# power_injector_0_7.net
KiCad netlist of a schematic drawn in EAGLE
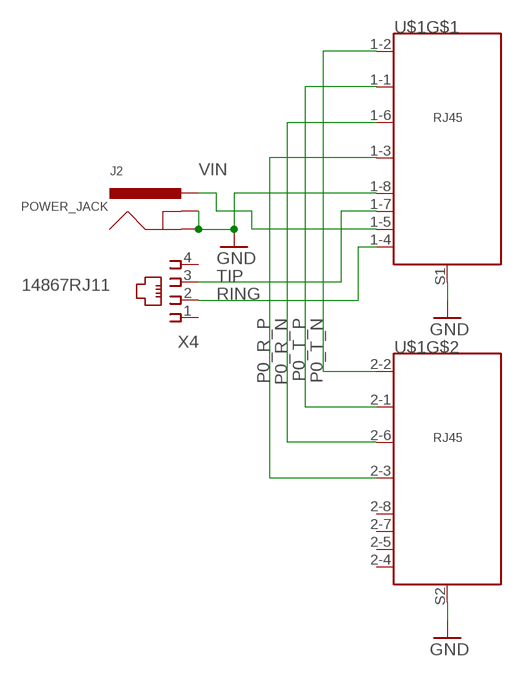
[diagram p0: schematic, sheet 1]

(export (version "E")
  (design (tool "Eeschema 10.0.6"))
  (components
    (comp (ref "J2")
      (value "POWER_JACK")
      (footprint "eagle-import:POWER_JACK_SLOT1")
      (libsource (lib "eagle-import") (part "POWER_JACK"))
    )
    (comp (ref "U$1")
      (value "ETHERNET_2PORT")
      (footprint "eagle-import:ETHERNET-1X2")
      (libsource (lib "eagle-import") (part "ETHERNET_2PORT"))
    )
    (comp (ref "X4")
      (value "14867RJ11")
      (footprint "eagle-import:14867")
      (libsource (lib "eagle-import") (part "14867RJ11"))
    )
  )
  (nets
    (net (code "1") (name "/P0_R_N") (class "Default")
      (node (ref "U$1") (pin "1-6") (pinfunction "6_1-6") (pintype "passive"))
      (node (ref "U$1") (pin "2-6") (pinfunction "6_2-6") (pintype "passive"))
    )
    (net (code "2") (name "/P0_R_P") (class "Default")
      (node (ref "U$1") (pin "1-3") (pinfunction "3_1-3") (pintype "passive"))
      (node (ref "U$1") (pin "2-3") (pinfunction "3_2-3") (pintype "passive"))
    )
    (net (code "3") (name "/P0_T_N") (class "Default")
      (node (ref "U$1") (pin "1-2") (pinfunction "2_1-2") (pintype "passive"))
      (node (ref "U$1") (pin "2-2") (pinfunction "2_2-2") (pintype "passive"))
    )
    (net (code "4") (name "/P0_T_P") (class "Default")
      (node (ref "U$1") (pin "1-1") (pinfunction "1_1-1") (pintype "passive"))
      (node (ref "U$1") (pin "2-1") (pinfunction "1_2-1") (pintype "passive"))
    )
    (net (code "5") (name "/RING") (class "Default")
      (node (ref "U$1") (pin "1-4") (pinfunction "4_1-4") (pintype "passive"))
      (node (ref "X4") (pin "2") (pinfunction "2_2") (pintype "passive"))
    )
    (net (code "6") (name "/TIP") (class "Default")
      (node (ref "U$1") (pin "1-7") (pinfunction "7_1-7") (pintype "passive"))
      (node (ref "X4") (pin "3") (pinfunction "3_3") (pintype "passive"))
    )
    (net (code "7") (name "/VIN") (class "Default")
      (node (ref "J2") (pin "PWR") (pinfunction "PWR_PWR") (pintype "bidirectional"))
      (node (ref "U$1") (pin "1-5") (pinfunction "5_1-5") (pintype "passive"))
    )
    (net (code "8") (name "GND") (class "Default")
      (node (ref "J2") (pin "GND@1") (pinfunction "GNDBREAK_GND@1") (pintype "bidirectional"))
      (node (ref "J2") (pin "GND@2") (pinfunction "GND_GND@2") (pintype "bidirectional"))
      (node (ref "U$1") (pin "1-8") (pinfunction "8_1-8") (pintype "passive"))
      (node (ref "U$1") (pin "S1") (pinfunction "SHIELD_S1") (pintype "power_in"))
      (node (ref "U$1") (pin "S2") (pinfunction "SHIELD_S2") (pintype "power_in"))
    )
    (net (code "9") (name "unconnected-(U$1B-4-Pad2-4)") (class "Default")
      (node (ref "U$1") (pin "2-4") (pinfunction "4_2-4") (pintype "passive"))
    )
    (net (code "10") (name "unconnected-(U$1B-5-Pad2-5)") (class "Default")
      (node (ref "U$1") (pin "2-5") (pinfunction "5_2-5") (pintype "passive"))
    )
    (net (code "11") (name "unconnected-(U$1B-7-Pad2-7)") (class "Default")
      (node (ref "U$1") (pin "2-7") (pinfunction "7_2-7") (pintype "passive"))
    )
    (net (code "12") (name "unconnected-(U$1B-8-Pad2-8)") (class "Default")
      (node (ref "U$1") (pin "2-8") (pinfunction "8_2-8") (pintype "passive"))
    )
    (net (code "13") (name "unconnected-(X4-Pad1)") (class "Default")
      (node (ref "X4") (pin "1") (pinfunction "1_1") (pintype "passive"))
    )
    (net (code "14") (name "unconnected-(X4-Pad4)") (class "Default")
      (node (ref "X4") (pin "4") (pinfunction "4_4") (pintype "passive"))
    )
  )
)
